# SolarPanelZPlus.net
KiCad netlist of a schematic drawn in Altium Designer
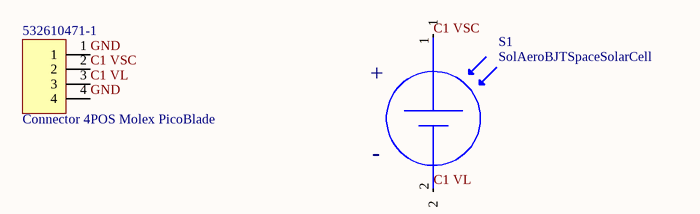
[diagram p0: SolarPanelZPlus.SchDoc]

(export (version "E")
  (design (tool "Eeschema 10.0.6"))
  (components
    (comp (ref "532610471-1")
      (value "Connector 4POS Molex PicoBlade")
      (footprint "532610471")
      (libsource (lib "SolarPanelZPlus") (part "532610471"))
    )
    (comp (ref "S1")
      (value "SolAeroBJTSpaceSolarCell")
      (libsource (lib "SolarPanelZPlus") (part "SolAeroBJTSpaceSolarCell"))
    )
  )
  (nets
    (net (code "1") (name "/C1 VL") (class "Default")
      (node (ref "532610471-1") (pin "3") (pinfunction "3_3") (pintype "passive"))
      (node (ref "S1") (pin "2") (pinfunction "2_2") (pintype "passive"))
    )
    (net (code "2") (name "/C1 VSC") (class "Default")
      (node (ref "532610471-1") (pin "2") (pinfunction "2_2") (pintype "passive"))
      (node (ref "S1") (pin "1") (pinfunction "1_1") (pintype "power_in"))
    )
    (net (code "3") (name "/GND") (class "Default")
      (node (ref "532610471-1") (pin "1") (pinfunction "1_1") (pintype "passive"))
      (node (ref "532610471-1") (pin "4") (pinfunction "4_4") (pintype "passive"))
    )
  )
)
